# 3_-DCDC-3V3.net
KiCad netlist of a schematic drawn in Altium Designer
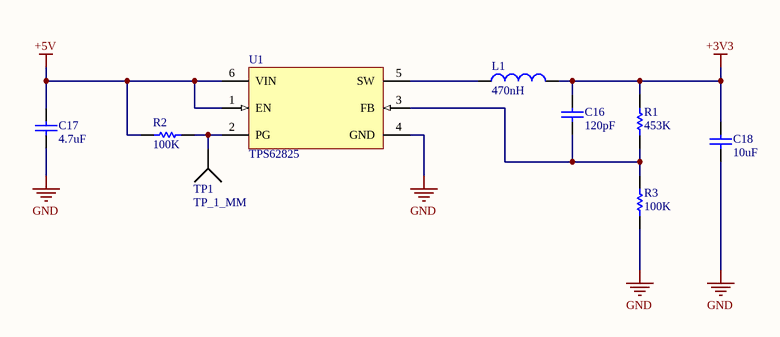
[diagram p0: [3]-DCDC-3V3.SchDoc]

(export (version "E")
  (design (tool "Eeschema 10.0.6"))
  (components
    (comp (ref "C16")
      (value "120pF")
      (footprint "CAPC1005N")
      (description "CAP CER 120PF 50V C0G/NP0 0402")
      (fields (field (name "TOLERANCE") "1 %") (field (name "VOLTAGE") "50V"))
      (libsource (lib "bitsnio") (part "GRM1555C1H121FA01D"))
    )
    (comp (ref "C17")
      (value "4.7uF")
      (footprint "CAPC2012N")
      (description "CAP CER 4.7UF 25V X5R 0805")
      (fields (field (name "TOLERANCE") "10%") (field (name "VOLTAGE") "25V"))
      (libsource (lib "bitsnio") (part "C2012X5R1E475K125AB"))
    )
    (comp (ref "C18")
      (value "10uF")
      (footprint "CAPC2012N")
      (description "CAP CER 10UF 10V X7R 0805")
      (fields (field (name "TOLERANCE") "10%") (field (name "VOLTAGE") "10V"))
      (libsource (lib "bitsnio") (part "C2012X7R1A106K125AC"))
    )
    (comp (ref "L1")
      (value "470nH")
      (footprint "IHLP-1212AE-11")
      (description "FIXED IND 470NH 6.7A 15 MOHM SMD")
      (fields (field (name "TOLERANCE") "20%"))
      (libsource (lib "bitsnio") (part "IHLP1212AEERR47M11"))
    )
    (comp (ref "R1")
      (value "453K")
      (footprint "RESC1005N")
      (description "RES SMD 453K OHM 1% 1/16W 0402")
      (fields
        (field (name "MANUFACTURER") "Stackpole Electronics")
        (field (name "MANUFACTURER PART NUMBER") "RMCF0402FT453K")
      )
      (libsource (lib "bitsnio") (part "RMCF0402FT453K"))
    )
    (comp (ref "R2")
      (value "100K")
      (footprint "RESC1005N")
      (description "RES SMD 100K OHM 1% 1/16W 0402")
      (fields (field (name "TOLERANCE") "1 %"))
      (libsource (lib "bitsnio") (part "RC0402FR-07100KL"))
    )
    (comp (ref "R3")
      (value "100K")
      (footprint "RESC1005N")
      (description "RES SMD 100K OHM 1% 1/16W 0402")
      (fields (field (name "TOLERANCE") "1 %"))
      (libsource (lib "bitsnio") (part "RC0402FR-07100KL"))
    )
    (comp (ref "TP1") (value "TP_1_MM") (footprint "TP_1_MM") (libsource (lib "bitsnio") (part "TP_1_MM")))
    (comp (ref "U1")
      (value "TPS62825")
      (footprint "DMQ0006A")
      (description "IC STEP DOWN CONV 1-5V 2A QFN")
      (libsource (lib "bitsnio") (part "IC_TPS62825DMQR"))
    )
  )
  (nets
    (net (code "1") (name "+3V3") (class "Default")
      (node (ref "C16") (pin "2") (pinfunction "2_2") (pintype "passive"))
      (node (ref "C18") (pin "2") (pinfunction "2_2") (pintype "passive"))
      (node (ref "L1") (pin "2") (pinfunction "2_2") (pintype "passive"))
      (node (ref "R1") (pin "2") (pinfunction "2_2") (pintype "passive"))
    )
    (net (code "2") (name "+5V") (class "Default")
      (node (ref "C17") (pin "2") (pinfunction "2_2") (pintype "passive"))
      (node (ref "R2") (pin "1") (pinfunction "1_1") (pintype "passive"))
      (node (ref "U1") (pin "1") (pinfunction "EN_1") (pintype "input"))
      (node (ref "U1") (pin "6") (pinfunction "VIN_6") (pintype "power_in"))
    )
    (net (code "3") (name "GND") (class "Default")
      (node (ref "C17") (pin "1") (pinfunction "1_1") (pintype "passive"))
      (node (ref "C18") (pin "1") (pinfunction "1_1") (pintype "passive"))
      (node (ref "R3") (pin "1") (pinfunction "1_1") (pintype "passive"))
      (node (ref "U1") (pin "4") (pinfunction "GND_4") (pintype "power_in"))
    )
    (net (code "4") (name "Net-(U1-FB)") (class "Default")
      (node (ref "C16") (pin "1") (pinfunction "1_1") (pintype "passive"))
      (node (ref "R1") (pin "1") (pinfunction "1_1") (pintype "passive"))
      (node (ref "R3") (pin "2") (pinfunction "2_2") (pintype "passive"))
      (node (ref "U1") (pin "3") (pinfunction "FB_3") (pintype "input"))
    )
    (net (code "5") (name "Net-(U1-PG)") (class "Default")
      (node (ref "R2") (pin "2") (pinfunction "2_2") (pintype "passive"))
      (node (ref "TP1") (pin "1") (pinfunction "1_1") (pintype "passive"))
      (node (ref "U1") (pin "2") (pinfunction "PG_2") (pintype "open_collector"))
    )
    (net (code "6") (name "Net-(U1-SW)") (class "Default")
      (node (ref "L1") (pin "1") (pinfunction "1_1") (pintype "passive"))
      (node (ref "U1") (pin "5") (pinfunction "SW_5") (pintype "power_in"))
    )
  )
)
